# Debug_Test_Points.net
KiCad netlist of a schematic drawn in Altium Designer
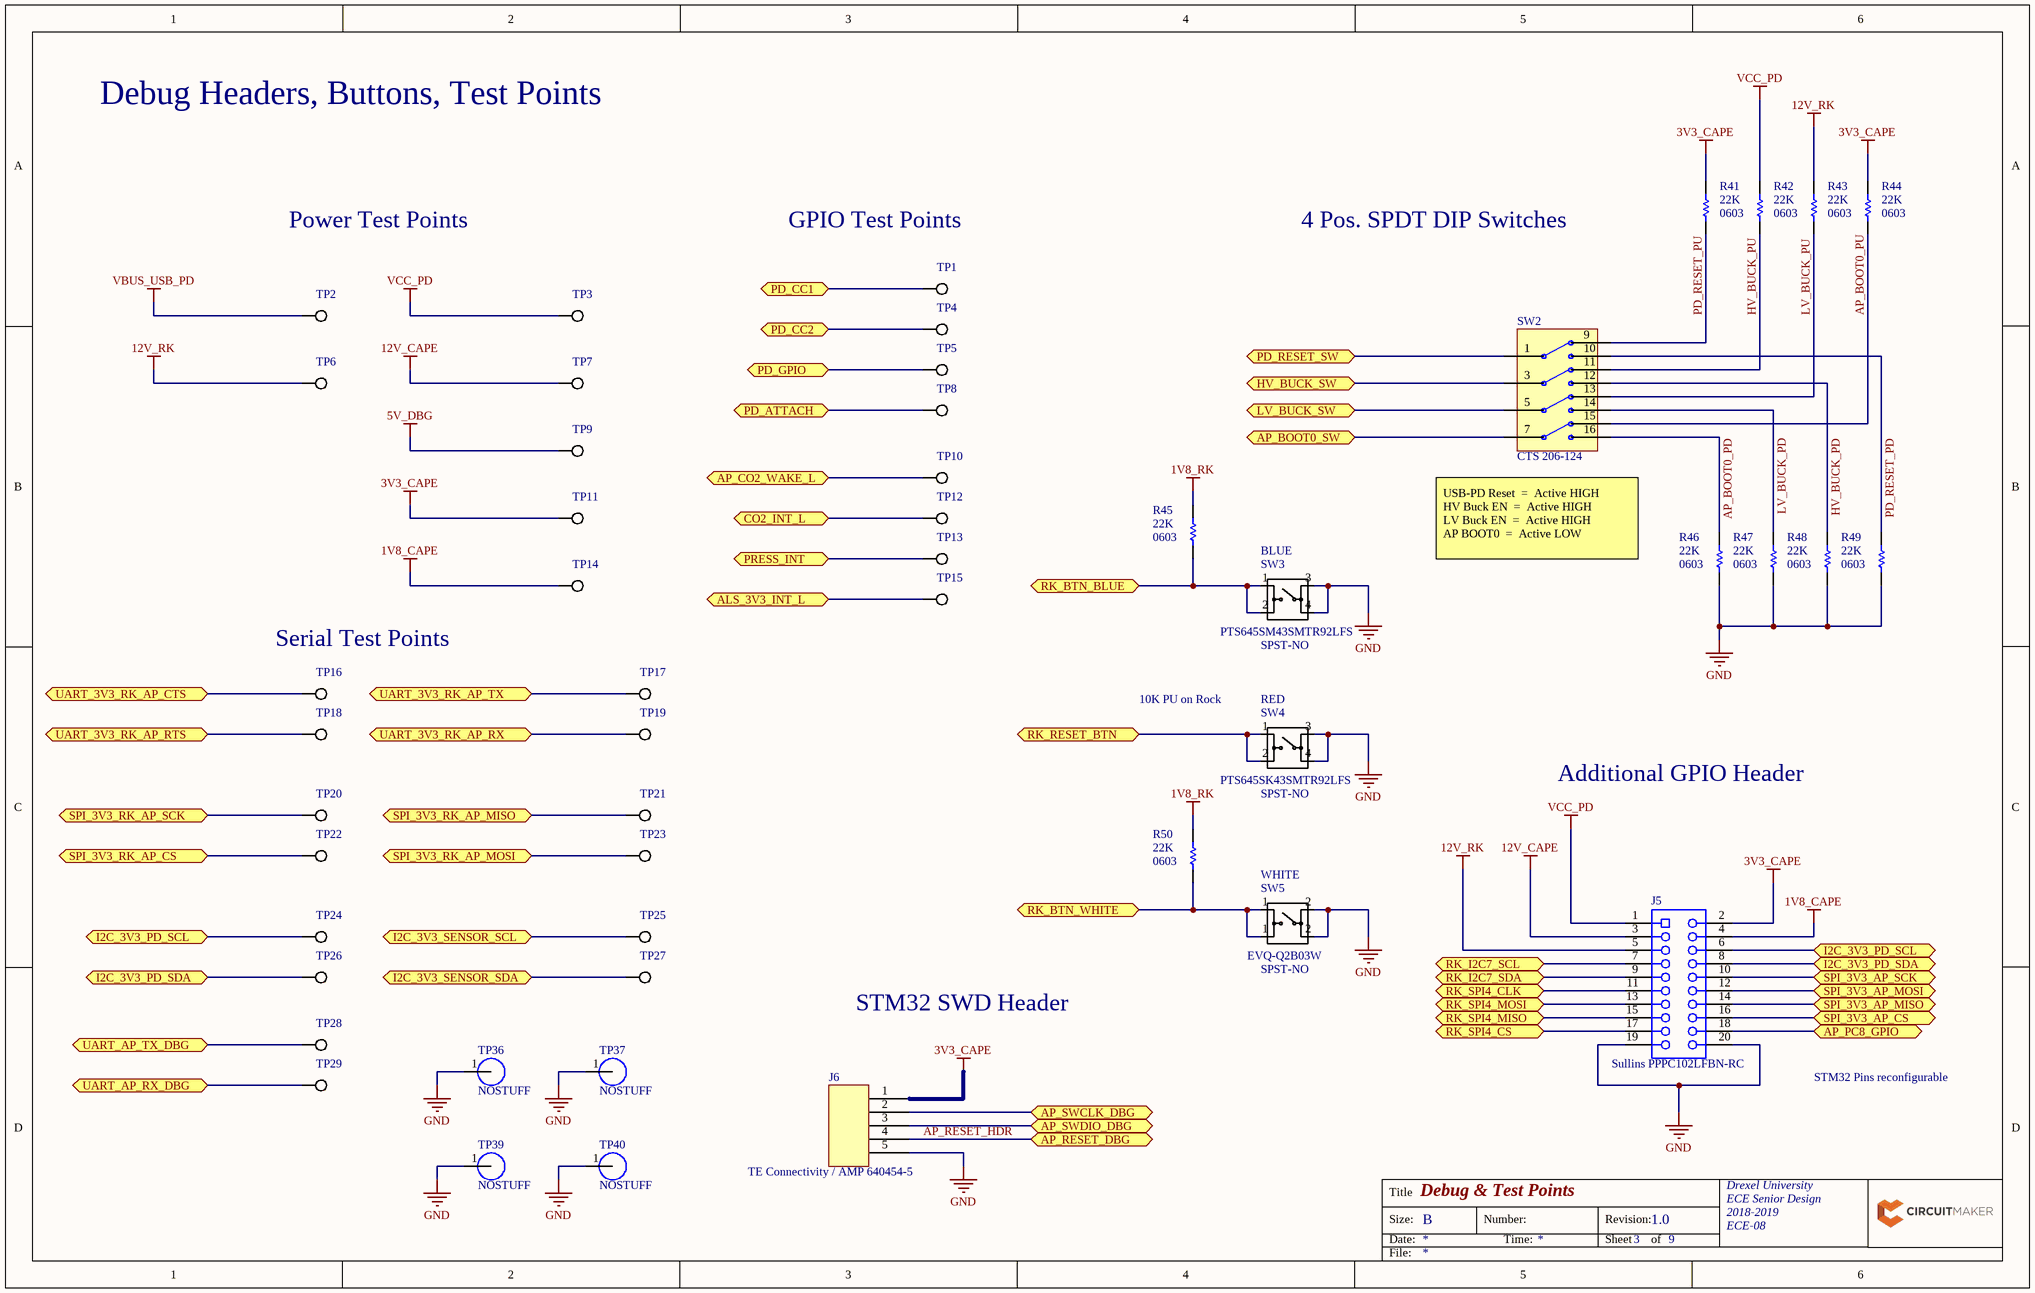
[diagram p0: Debug & Test Points.SchDoc]

(export (version "E")
  (design (tool "Eeschema 10.0.6"))
  (components
    (comp (ref "J5")
      (value "Sullins PPPC102LFBN-RC")
      (footprint "SLIN-PPPC102LFBN-RC_V")
      (fields (field (name "MANUFACTURER PART NUMBER") "PPPC102LFBN-RC"))
      (libsource (lib "CommunityVault") (part "CN-2P-F-R20"))
    )
    (comp (ref "J6")
      (value "TE Connectivity / AMP 640454-5")
      (footprint "PCB-cjz7utnpmh9dagnjcosy-1")
      (description "MTA-100 5 Position 2.54 mm Single Row Through-Hole Straight Wire to Board Header")
      (fields (field (name "MANUFACTURER PART NUMBER") "640454-5"))
      (libsource (lib "CommunityVault") (part "AMP-640454-5"))
    )
    (comp (ref "R41")
      (value "Yageo RC0603FR-0722KL")
      (footprint "RESC1608X55X25LL10T15")
      (description "Chip Resistor, 22 KOhm, +/- 1%, 0.1 W, -55 to 155 degC, 0603 (1608 Metric), RoHS, Tape and Reel")
      (fields
        (field (name "RESISTANCE") "22K")
        (field (name "CASE/PACKAGE") "0603")
        (field (name "MANUFACTURER PART NUMBER") "RC0603FR-0722KL")
      )
      (libsource (lib "CommunityVault") (part "CMP-1853446-5"))
    )
    (comp (ref "R42")
      (value "Yageo RC0603FR-0722KL")
      (footprint "RESC1608X55X25LL10T15")
      (description "Chip Resistor, 22 KOhm, +/- 1%, 0.1 W, -55 to 155 degC, 0603 (1608 Metric), RoHS, Tape and Reel")
      (fields
        (field (name "RESISTANCE") "22K")
        (field (name "CASE/PACKAGE") "0603")
        (field (name "MANUFACTURER PART NUMBER") "RC0603FR-0722KL")
      )
      (libsource (lib "CommunityVault") (part "CMP-1853446-5"))
    )
    (comp (ref "R43")
      (value "Yageo RC0603FR-0722KL")
      (footprint "RESC1608X55X25LL10T15")
      (description "Chip Resistor, 22 KOhm, +/- 1%, 0.1 W, -55 to 155 degC, 0603 (1608 Metric), RoHS, Tape and Reel")
      (fields
        (field (name "RESISTANCE") "22K")
        (field (name "CASE/PACKAGE") "0603")
        (field (name "MANUFACTURER PART NUMBER") "RC0603FR-0722KL")
      )
      (libsource (lib "CommunityVault") (part "CMP-1853446-5"))
    )
    (comp (ref "R44")
      (value "Yageo RC0603FR-0722KL")
      (footprint "RESC1608X55X25LL10T15")
      (description "Chip Resistor, 22 KOhm, +/- 1%, 0.1 W, -55 to 155 degC, 0603 (1608 Metric), RoHS, Tape and Reel")
      (fields
        (field (name "RESISTANCE") "22K")
        (field (name "CASE/PACKAGE") "0603")
        (field (name "MANUFACTURER PART NUMBER") "RC0603FR-0722KL")
      )
      (libsource (lib "CommunityVault") (part "CMP-1853446-5"))
    )
    (comp (ref "R45")
      (value "Yageo RC0603FR-0722KL")
      (footprint "RESC1608X55X25LL10T15")
      (description "Chip Resistor, 22 KOhm, +/- 1%, 0.1 W, -55 to 155 degC, 0603 (1608 Metric), RoHS, Tape and Reel")
      (fields
        (field (name "RESISTANCE") "22K")
        (field (name "CASE/PACKAGE") "0603")
        (field (name "MANUFACTURER PART NUMBER") "RC0603FR-0722KL")
      )
      (libsource (lib "CommunityVault") (part "CMP-1853446-5"))
    )
    (comp (ref "R46")
      (value "Yageo RC0603FR-0722KL")
      (footprint "RESC1608X55X25LL10T15")
      (description "Chip Resistor, 22 KOhm, +/- 1%, 0.1 W, -55 to 155 degC, 0603 (1608 Metric), RoHS, Tape and Reel")
      (fields
        (field (name "RESISTANCE") "22K")
        (field (name "CASE/PACKAGE") "0603")
        (field (name "MANUFACTURER PART NUMBER") "RC0603FR-0722KL")
      )
      (libsource (lib "CommunityVault") (part "CMP-1853446-5"))
    )
    (comp (ref "R47")
      (value "Yageo RC0603FR-0722KL")
      (footprint "RESC1608X55X25LL10T15")
      (description "Chip Resistor, 22 KOhm, +/- 1%, 0.1 W, -55 to 155 degC, 0603 (1608 Metric), RoHS, Tape and Reel")
      (fields
        (field (name "RESISTANCE") "22K")
        (field (name "CASE/PACKAGE") "0603")
        (field (name "MANUFACTURER PART NUMBER") "RC0603FR-0722KL")
      )
      (libsource (lib "CommunityVault") (part "CMP-1853446-5"))
    )
    (comp (ref "R48")
      (value "Yageo RC0603FR-0722KL")
      (footprint "RESC1608X55X25LL10T15")
      (description "Chip Resistor, 22 KOhm, +/- 1%, 0.1 W, -55 to 155 degC, 0603 (1608 Metric), RoHS, Tape and Reel")
      (fields
        (field (name "RESISTANCE") "22K")
        (field (name "CASE/PACKAGE") "0603")
        (field (name "MANUFACTURER PART NUMBER") "RC0603FR-0722KL")
      )
      (libsource (lib "CommunityVault") (part "CMP-1853446-5"))
    )
    (comp (ref "R49")
      (value "Yageo RC0603FR-0722KL")
      (footprint "RESC1608X55X25LL10T15")
      (description "Chip Resistor, 22 KOhm, +/- 1%, 0.1 W, -55 to 155 degC, 0603 (1608 Metric), RoHS, Tape and Reel")
      (fields
        (field (name "RESISTANCE") "22K")
        (field (name "CASE/PACKAGE") "0603")
        (field (name "MANUFACTURER PART NUMBER") "RC0603FR-0722KL")
      )
      (libsource (lib "CommunityVault") (part "CMP-1853446-5"))
    )
    (comp (ref "R50")
      (value "Yageo RC0603FR-0722KL")
      (footprint "RESC1608X55X25LL10T15")
      (description "Chip Resistor, 22 KOhm, +/- 1%, 0.1 W, -55 to 155 degC, 0603 (1608 Metric), RoHS, Tape and Reel")
      (fields
        (field (name "RESISTANCE") "22K")
        (field (name "CASE/PACKAGE") "0603")
        (field (name "MANUFACTURER PART NUMBER") "RC0603FR-0722KL")
      )
      (libsource (lib "CommunityVault") (part "CMP-1853446-5"))
    )
    (comp (ref "SW2")
      (value "CTS 206-124")
      (footprint "PCB-nbvsi55tyuro9im52r90-1")
      (description "Switch DIP OFF ON SPDT 4 Raised Slide 0.05A 24VDC PC Pins 10000Cycles 2.54mm Thru-Hole Tube")
      (fields (field (name "MANUFACTURER PART NUMBER") "206-124"))
      (libsource (lib "CommunityVault") (part "CMP-9d2d5432b3d942ea-1"))
    )
    (comp (ref "SW3")
      (value "C&K Components PTS645SM43SMTR92LFS")
      (footprint "PCB-s4cw3ztviwh2470uqn6q-1")
      (description "Switch Tactile N.O. SPST Round Button Gull Wing 0.05A 12VDC 100000Cycles 1.57N SMD T/R")
      (fields
        (field (name "MANUFACTURER PART NUMBER") "PTS645SM43SMTR92LFS")
        (field (name "CONTACTS TYPE") "SPST-NO")
      )
      (libsource (lib "CommunityVault") (part "CMP-3c47f600356ce380-14"))
    )
    (comp (ref "SW4")
      (value "C&K Components PTS645SK43SMTR92LFS")
      (footprint "PCB-2l25iuk5dcek232nr8ss-1")
      (description "Switch Tactile N.O SPST Round Button Gull Wing 0.05A 12VDC 100000Cycle 2.55N SMD T/R")
      (fields
        (field (name "MANUFACTURER PART NUMBER") "PTS645SK43SMTR92LFS")
        (field (name "CONTACTS TYPE") "SPST-NO")
      )
      (libsource (lib "CommunityVault") (part "CMP-8f9845df1015505f-1"))
    )
    (comp (ref "SW5")
      (value "Panasonic EVQ-Q2B03W")
      (footprint "PCB-772q97a3nev1hwheshwj-1")
      (description "Switch Tactile ON OFF SPST Round Button J-Bend 0.02A 15VDC 0.5N SMD Embossed T/R")
      (fields (field (name "MANUFACTURER PART NUMBER") "EVQ-Q2B03W") (field (name "CONTACTS TYPE") "SPST-NO"))
      (libsource (lib "CommunityVault") (part "CMP-0c8bc5972372d34c-1"))
    )
    (comp (ref "TP1")
      (value "SYM-r3tntvff39g057zxjnnx-1")
      (footprint "PCB-hew5anfrhkqvtgt23eko-1")
      (description "SMT Pad Test Point 1.27mm Diameter")
      (libsource (lib "CommunityVault") (part "SYM-r3tntvff39g057zxjnnx-1"))
    )
    (comp (ref "TP2")
      (value "SYM-r3tntvff39g057zxjnnx-1")
      (footprint "PCB-hew5anfrhkqvtgt23eko-1")
      (description "SMT Pad Test Point 1.27mm Diameter")
      (libsource (lib "CommunityVault") (part "SYM-r3tntvff39g057zxjnnx-1"))
    )
    (comp (ref "TP3")
      (value "SYM-r3tntvff39g057zxjnnx-1")
      (footprint "PCB-hew5anfrhkqvtgt23eko-1")
      (description "SMT Pad Test Point 1.27mm Diameter")
      (libsource (lib "CommunityVault") (part "SYM-r3tntvff39g057zxjnnx-1"))
    )
    (comp (ref "TP4")
      (value "SYM-r3tntvff39g057zxjnnx-1")
      (footprint "PCB-hew5anfrhkqvtgt23eko-1")
      (description "SMT Pad Test Point 1.27mm Diameter")
      (libsource (lib "CommunityVault") (part "SYM-r3tntvff39g057zxjnnx-1"))
    )
    (comp (ref "TP5")
      (value "SYM-r3tntvff39g057zxjnnx-1")
      (footprint "PCB-hew5anfrhkqvtgt23eko-1")
      (description "SMT Pad Test Point 1.27mm Diameter")
      (libsource (lib "CommunityVault") (part "SYM-r3tntvff39g057zxjnnx-1"))
    )
    (comp (ref "TP6")
      (value "SYM-r3tntvff39g057zxjnnx-1")
      (footprint "PCB-hew5anfrhkqvtgt23eko-1")
      (description "SMT Pad Test Point 1.27mm Diameter")
      (libsource (lib "CommunityVault") (part "SYM-r3tntvff39g057zxjnnx-1"))
    )
    (comp (ref "TP7")
      (value "SYM-r3tntvff39g057zxjnnx-1")
      (footprint "PCB-hew5anfrhkqvtgt23eko-1")
      (description "SMT Pad Test Point 1.27mm Diameter")
      (libsource (lib "CommunityVault") (part "SYM-r3tntvff39g057zxjnnx-1"))
    )
    (comp (ref "TP8")
      (value "SYM-r3tntvff39g057zxjnnx-1")
      (footprint "PCB-hew5anfrhkqvtgt23eko-1")
      (description "SMT Pad Test Point 1.27mm Diameter")
      (libsource (lib "CommunityVault") (part "SYM-r3tntvff39g057zxjnnx-1"))
    )
    (comp (ref "TP9")
      (value "SYM-r3tntvff39g057zxjnnx-1")
      (footprint "PCB-hew5anfrhkqvtgt23eko-1")
      (description "SMT Pad Test Point 1.27mm Diameter")
      (libsource (lib "CommunityVault") (part "SYM-r3tntvff39g057zxjnnx-1"))
    )
    (comp (ref "TP10")
      (value "SYM-r3tntvff39g057zxjnnx-1")
      (footprint "PCB-hew5anfrhkqvtgt23eko-1")
      (description "SMT Pad Test Point 1.27mm Diameter")
      (libsource (lib "CommunityVault") (part "SYM-r3tntvff39g057zxjnnx-1"))
    )
    (comp (ref "TP11")
      (value "SYM-r3tntvff39g057zxjnnx-1")
      (footprint "PCB-hew5anfrhkqvtgt23eko-1")
      (description "SMT Pad Test Point 1.27mm Diameter")
      (libsource (lib "CommunityVault") (part "SYM-r3tntvff39g057zxjnnx-1"))
    )
    (comp (ref "TP12")
      (value "SYM-r3tntvff39g057zxjnnx-1")
      (footprint "PCB-hew5anfrhkqvtgt23eko-1")
      (description "SMT Pad Test Point 1.27mm Diameter")
      (libsource (lib "CommunityVault") (part "SYM-r3tntvff39g057zxjnnx-1"))
    )
    (comp (ref "TP13")
      (value "SYM-r3tntvff39g057zxjnnx-1")
      (footprint "PCB-hew5anfrhkqvtgt23eko-1")
      (description "SMT Pad Test Point 1.27mm Diameter")
      (libsource (lib "CommunityVault") (part "SYM-r3tntvff39g057zxjnnx-1"))
    )
    (comp (ref "TP14")
      (value "SYM-r3tntvff39g057zxjnnx-1")
      (footprint "PCB-hew5anfrhkqvtgt23eko-1")
      (description "SMT Pad Test Point 1.27mm Diameter")
      (libsource (lib "CommunityVault") (part "SYM-r3tntvff39g057zxjnnx-1"))
    )
    (comp (ref "TP15")
      (value "SYM-r3tntvff39g057zxjnnx-1")
      (footprint "PCB-hew5anfrhkqvtgt23eko-1")
      (description "SMT Pad Test Point 1.27mm Diameter")
      (libsource (lib "CommunityVault") (part "SYM-r3tntvff39g057zxjnnx-1"))
    )
    (comp (ref "TP16")
      (value "SYM-r3tntvff39g057zxjnnx-1")
      (footprint "PCB-hew5anfrhkqvtgt23eko-1")
      (description "SMT Pad Test Point 1.27mm Diameter")
      (libsource (lib "CommunityVault") (part "SYM-r3tntvff39g057zxjnnx-1"))
    )
    (comp (ref "TP17")
      (value "SYM-r3tntvff39g057zxjnnx-1")
      (footprint "PCB-hew5anfrhkqvtgt23eko-1")
      (description "SMT Pad Test Point 1.27mm Diameter")
      (libsource (lib "CommunityVault") (part "SYM-r3tntvff39g057zxjnnx-1"))
    )
    (comp (ref "TP18")
      (value "SYM-r3tntvff39g057zxjnnx-1")
      (footprint "PCB-hew5anfrhkqvtgt23eko-1")
      (description "SMT Pad Test Point 1.27mm Diameter")
      (libsource (lib "CommunityVault") (part "SYM-r3tntvff39g057zxjnnx-1"))
    )
    (comp (ref "TP19")
      (value "SYM-r3tntvff39g057zxjnnx-1")
      (footprint "PCB-hew5anfrhkqvtgt23eko-1")
      (description "SMT Pad Test Point 1.27mm Diameter")
      (libsource (lib "CommunityVault") (part "SYM-r3tntvff39g057zxjnnx-1"))
    )
    (comp (ref "TP20")
      (value "SYM-r3tntvff39g057zxjnnx-1")
      (footprint "PCB-hew5anfrhkqvtgt23eko-1")
      (description "SMT Pad Test Point 1.27mm Diameter")
      (libsource (lib "CommunityVault") (part "SYM-r3tntvff39g057zxjnnx-1"))
    )
    (comp (ref "TP21")
      (value "SYM-r3tntvff39g057zxjnnx-1")
      (footprint "PCB-hew5anfrhkqvtgt23eko-1")
      (description "SMT Pad Test Point 1.27mm Diameter")
      (libsource (lib "CommunityVault") (part "SYM-r3tntvff39g057zxjnnx-1"))
    )
    (comp (ref "TP22")
      (value "SYM-r3tntvff39g057zxjnnx-1")
      (footprint "PCB-hew5anfrhkqvtgt23eko-1")
      (description "SMT Pad Test Point 1.27mm Diameter")
      (libsource (lib "CommunityVault") (part "SYM-r3tntvff39g057zxjnnx-1"))
    )
    (comp (ref "TP23")
      (value "SYM-r3tntvff39g057zxjnnx-1")
      (footprint "PCB-hew5anfrhkqvtgt23eko-1")
      (description "SMT Pad Test Point 1.27mm Diameter")
      (libsource (lib "CommunityVault") (part "SYM-r3tntvff39g057zxjnnx-1"))
    )
    (comp (ref "TP24")
      (value "SYM-r3tntvff39g057zxjnnx-1")
      (footprint "PCB-hew5anfrhkqvtgt23eko-1")
      (description "SMT Pad Test Point 1.27mm Diameter")
      (libsource (lib "CommunityVault") (part "SYM-r3tntvff39g057zxjnnx-1"))
    )
    (comp (ref "TP25")
      (value "SYM-r3tntvff39g057zxjnnx-1")
      (footprint "PCB-hew5anfrhkqvtgt23eko-1")
      (description "SMT Pad Test Point 1.27mm Diameter")
      (libsource (lib "CommunityVault") (part "SYM-r3tntvff39g057zxjnnx-1"))
    )
    (comp (ref "TP26")
      (value "SYM-r3tntvff39g057zxjnnx-1")
      (footprint "PCB-hew5anfrhkqvtgt23eko-1")
      (description "SMT Pad Test Point 1.27mm Diameter")
      (libsource (lib "CommunityVault") (part "SYM-r3tntvff39g057zxjnnx-1"))
    )
    (comp (ref "TP27")
      (value "SYM-r3tntvff39g057zxjnnx-1")
      (footprint "PCB-hew5anfrhkqvtgt23eko-1")
      (description "SMT Pad Test Point 1.27mm Diameter")
      (libsource (lib "CommunityVault") (part "SYM-r3tntvff39g057zxjnnx-1"))
    )
    (comp (ref "TP28")
      (value "SYM-r3tntvff39g057zxjnnx-1")
      (footprint "PCB-hew5anfrhkqvtgt23eko-1")
      (description "SMT Pad Test Point 1.27mm Diameter")
      (libsource (lib "CommunityVault") (part "SYM-r3tntvff39g057zxjnnx-1"))
    )
    (comp (ref "TP29")
      (value "SYM-r3tntvff39g057zxjnnx-1")
      (footprint "PCB-hew5anfrhkqvtgt23eko-1")
      (description "SMT Pad Test Point 1.27mm Diameter")
      (libsource (lib "CommunityVault") (part "SYM-r3tntvff39g057zxjnnx-1"))
    )
    (comp (ref "TP36")
      (value "Keystone 5015")
      (footprint "PCB-57fxnr3lnfj79tb7d57h-1")
      (description "Test Point; Micro Mini; SMT; Phos Bronze/Silver; 1000pc Tape & Reel")
      (fields (field (name "ALTIUM_UNNAMED_1") "NOSTUFF"))
      (libsource (lib "CommunityVault") (part "CMP-0dc8c4c22640d20f-15"))
    )
    (comp (ref "TP37")
      (value "Keystone 5015")
      (footprint "PCB-57fxnr3lnfj79tb7d57h-1")
      (description "Test Point; Micro Mini; SMT; Phos Bronze/Silver; 1000pc Tape & Reel")
      (fields (field (name "ALTIUM_UNNAMED_1") "NOSTUFF"))
      (libsource (lib "CommunityVault") (part "CMP-0dc8c4c22640d20f-15"))
    )
    (comp (ref "TP39")
      (value "Keystone 5015")
      (footprint "PCB-57fxnr3lnfj79tb7d57h-1")
      (description "Test Point; Micro Mini; SMT; Phos Bronze/Silver; 1000pc Tape & Reel")
      (fields (field (name "ALTIUM_UNNAMED_1") "NOSTUFF"))
      (libsource (lib "CommunityVault") (part "CMP-0dc8c4c22640d20f-15"))
    )
    (comp (ref "TP40")
      (value "Keystone 5015")
      (footprint "PCB-57fxnr3lnfj79tb7d57h-1")
      (description "Test Point; Micro Mini; SMT; Phos Bronze/Silver; 1000pc Tape & Reel")
      (fields (field (name "ALTIUM_UNNAMED_1") "NOSTUFF"))
      (libsource (lib "CommunityVault") (part "CMP-0dc8c4c22640d20f-15"))
    )
  )
  (nets
    (net (code "1") (name "/ALS_3V3_INT_L") (class "Default")
      (node (ref "TP15") (pin "1") (pinfunction "1_1") (pintype "passive"))
    )
    (net (code "2") (name "/AP_BOOT0_PD") (class "Default")
      (node (ref "R46") (pin "2") (pinfunction "2_2") (pintype "passive"))
      (node (ref "SW2") (pin "16") (pinfunction "16_16") (pintype "passive"))
    )
    (net (code "3") (name "/AP_BOOT0_PU") (class "Default")
      (node (ref "R44") (pin "1") (pinfunction "1_1") (pintype "passive"))
      (node (ref "SW2") (pin "15") (pinfunction "15_15") (pintype "passive"))
    )
    (net (code "4") (name "/AP_BOOT0_SW") (class "Default")
      (node (ref "SW2") (pin "7") (pinfunction "7_7") (pintype "passive"))
    )
    (net (code "5") (name "/AP_CO2_WAKE_L") (class "Default")
      (node (ref "TP10") (pin "1") (pinfunction "1_1") (pintype "passive"))
    )
    (net (code "6") (name "/AP_PC8_GPIO") (class "Default")
      (node (ref "J5") (pin "18") (pinfunction "18_18") (pintype "passive"))
    )
    (net (code "7") (name "/AP_RESET_HDR") (class "Default")
      (node (ref "J6") (pin "4") (pinfunction "4_4") (pintype "passive"))
    )
    (net (code "8") (name "/AP_SWCLK_DBG") (class "Default")
      (node (ref "J6") (pin "2") (pinfunction "2_2") (pintype "passive"))
    )
    (net (code "9") (name "/AP_SWDIO_DBG") (class "Default")
      (node (ref "J6") (pin "3") (pinfunction "3_3") (pintype "passive"))
    )
    (net (code "10") (name "/CO2_INT_L") (class "Default")
      (node (ref "TP12") (pin "1") (pinfunction "1_1") (pintype "passive"))
    )
    (net (code "11") (name "/HV_BUCK_PD") (class "Default")
      (node (ref "R48") (pin "2") (pinfunction "2_2") (pintype "passive"))
      (node (ref "SW2") (pin "12") (pinfunction "12_12") (pintype "passive"))
    )
    (net (code "12") (name "/HV_BUCK_PU") (class "Default")
      (node (ref "R42") (pin "1") (pinfunction "1_1") (pintype "passive"))
      (node (ref "SW2") (pin "11") (pinfunction "11_11") (pintype "passive"))
    )
    (net (code "13") (name "/HV_BUCK_SW") (class "Default")
      (node (ref "SW2") (pin "3") (pinfunction "3_3") (pintype "passive"))
    )
    (net (code "14") (name "/I2C_3V3_PD_SCL") (class "Default")
      (node (ref "J5") (pin "6") (pinfunction "6_6") (pintype "passive"))
      (node (ref "TP24") (pin "1") (pinfunction "1_1") (pintype "passive"))
    )
    (net (code "15") (name "/I2C_3V3_PD_SDA") (class "Default")
      (node (ref "J5") (pin "8") (pinfunction "8_8") (pintype "passive"))
      (node (ref "TP26") (pin "1") (pinfunction "1_1") (pintype "passive"))
    )
    (net (code "16") (name "/I2C_3V3_SENSOR_SCL") (class "Default")
      (node (ref "TP25") (pin "1") (pinfunction "1_1") (pintype "passive"))
    )
    (net (code "17") (name "/I2C_3V3_SENSOR_SDA") (class "Default")
      (node (ref "TP27") (pin "1") (pinfunction "1_1") (pintype "passive"))
    )
    (net (code "18") (name "/LV_BUCK_PD") (class "Default")
      (node (ref "R47") (pin "2") (pinfunction "2_2") (pintype "passive"))
      (node (ref "SW2") (pin "14") (pinfunction "14_14") (pintype "passive"))
    )
    (net (code "19") (name "/LV_BUCK_PU") (class "Default")
      (node (ref "R43") (pin "1") (pinfunction "1_1") (pintype "passive"))
      (node (ref "SW2") (pin "13") (pinfunction "13_13") (pintype "passive"))
    )
    (net (code "20") (name "/LV_BUCK_SW") (class "Default")
      (node (ref "SW2") (pin "5") (pinfunction "5_5") (pintype "passive"))
    )
    (net (code "21") (name "/PD_ATTACH") (class "Default")
      (node (ref "TP8") (pin "1") (pinfunction "1_1") (pintype "passive"))
    )
    (net (code "22") (name "/PD_CC1") (class "Default")
      (node (ref "TP1") (pin "1") (pinfunction "1_1") (pintype "passive"))
    )
    (net (code "23") (name "/PD_CC2") (class "Default")
      (node (ref "TP4") (pin "1") (pinfunction "1_1") (pintype "passive"))
    )
    (net (code "24") (name "/PD_GPIO") (class "Default")
      (node (ref "TP5") (pin "1") (pinfunction "1_1") (pintype "passive"))
    )
    (net (code "25") (name "/PD_RESET_PD") (class "Default")
      (node (ref "R49") (pin "2") (pinfunction "2_2") (pintype "passive"))
      (node (ref "SW2") (pin "10") (pinfunction "10_10") (pintype "passive"))
    )
    (net (code "26") (name "/PD_RESET_PU") (class "Default")
      (node (ref "R41") (pin "1") (pinfunction "1_1") (pintype "passive"))
      (node (ref "SW2") (pin "9") (pinfunction "9_9") (pintype "passive"))
    )
    (net (code "27") (name "/PD_RESET_SW") (class "Default")
      (node (ref "SW2") (pin "1") (pinfunction "1_1") (pintype "passive"))
    )
    (net (code "28") (name "/PRESS_INT") (class "Default")
      (node (ref "TP13") (pin "1") (pinfunction "1_1") (pintype "passive"))
    )
    (net (code "29") (name "/RK_BTN_BLUE") (class "Default")
      (node (ref "R45") (pin "1") (pinfunction "1_1") (pintype "passive"))
      (node (ref "SW3") (pin "1") (pinfunction "1_1") (pintype "passive"))
      (node (ref "SW3") (pin "2") (pinfunction "2_2") (pintype "passive"))
    )
    (net (code "30") (name "/RK_BTN_WHITE") (class "Default")
      (node (ref "R50") (pin "1") (pinfunction "1_1") (pintype "passive"))
      (node (ref "SW5") (pin "1") (pinfunction "1_1") (pintype "passive"))
    )
    (net (code "31") (name "/RK_I2C7_SCL") (class "Default")
      (node (ref "J5") (pin "7") (pinfunction "7_7") (pintype "passive"))
    )
    (net (code "32") (name "/RK_I2C7_SDA") (class "Default")
      (node (ref "J5") (pin "9") (pinfunction "9_9") (pintype "passive"))
    )
    (net (code "33") (name "/RK_RESET_BTN") (class "Default")
      (node (ref "SW4") (pin "1") (pinfunction "1_1") (pintype "passive"))
      (node (ref "SW4") (pin "2") (pinfunction "2_2") (pintype "passive"))
    )
    (net (code "34") (name "/RK_SPI4_CLK") (class "Default")
      (node (ref "J5") (pin "11") (pinfunction "11_11") (pintype "passive"))
    )
    (net (code "35") (name "/RK_SPI4_CS") (class "Default")
      (node (ref "J5") (pin "17") (pinfunction "17_17") (pintype "passive"))
    )
    (net (code "36") (name "/RK_SPI4_MISO") (class "Default")
      (node (ref "J5") (pin "15") (pinfunction "15_15") (pintype "passive"))
    )
    (net (code "37") (name "/RK_SPI4_MOSI") (class "Default")
      (node (ref "J5") (pin "13") (pinfunction "13_13") (pintype "passive"))
    )
    (net (code "38") (name "/SPI_3V3_AP_CS") (class "Default")
      (node (ref "J5") (pin "16") (pinfunction "16_16") (pintype "passive"))
    )
    (net (code "39") (name "/SPI_3V3_AP_MISO") (class "Default")
      (node (ref "J5") (pin "14") (pinfunction "14_14") (pintype "passive"))
    )
    (net (code "40") (name "/SPI_3V3_AP_MOSI") (class "Default")
      (node (ref "J5") (pin "12") (pinfunction "12_12") (pintype "passive"))
    )
    (net (code "41") (name "/SPI_3V3_AP_SCK") (class "Default")
      (node (ref "J5") (pin "10") (pinfunction "10_10") (pintype "passive"))
    )
    (net (code "42") (name "/SPI_3V3_RK_AP_CS") (class "Default")
      (node (ref "TP22") (pin "1") (pinfunction "1_1") (pintype "passive"))
    )
    (net (code "43") (name "/SPI_3V3_RK_AP_MISO") (class "Default")
      (node (ref "TP21") (pin "1") (pinfunction "1_1") (pintype "passive"))
    )
    (net (code "44") (name "/SPI_3V3_RK_AP_MOSI") (class "Default")
      (node (ref "TP23") (pin "1") (pinfunction "1_1") (pintype "passive"))
    )
    (net (code "45") (name "/SPI_3V3_RK_AP_SCK") (class "Default")
      (node (ref "TP20") (pin "1") (pinfunction "1_1") (pintype "passive"))
    )
    (net (code "46") (name "/UART_3V3_RK_AP_CTS") (class "Default")
      (node (ref "TP16") (pin "1") (pinfunction "1_1") (pintype "passive"))
    )
    (net (code "47") (name "/UART_3V3_RK_AP_RTS") (class "Default")
      (node (ref "TP18") (pin "1") (pinfunction "1_1") (pintype "passive"))
    )
    (net (code "48") (name "/UART_3V3_RK_AP_RX") (class "Default")
      (node (ref "TP19") (pin "1") (pinfunction "1_1") (pintype "passive"))
    )
    (net (code "49") (name "/UART_3V3_RK_AP_TX") (class "Default")
      (node (ref "TP17") (pin "1") (pinfunction "1_1") (pintype "passive"))
    )
    (net (code "50") (name "/UART_AP_RX_DBG") (class "Default")
      (node (ref "TP29") (pin "1") (pinfunction "1_1") (pintype "passive"))
    )
    (net (code "51") (name "/UART_AP_TX_DBG") (class "Default")
      (node (ref "TP28") (pin "1") (pinfunction "1_1") (pintype "passive"))
    )
    (net (code "52") (name "1V8_CAPE") (class "Default")
      (node (ref "J5") (pin "4") (pinfunction "4_4") (pintype "passive"))
      (node (ref "TP14") (pin "1") (pinfunction "1_1") (pintype "passive"))
    )
    (net (code "53") (name "1V8_RK") (class "Default")
      (node (ref "R45") (pin "2") (pinfunction "2_2") (pintype "passive"))
      (node (ref "R50") (pin "2") (pinfunction "2_2") (pintype "passive"))
    )
    (net (code "54") (name "3V3_CAPE") (class "Default")
      (node (ref "J5") (pin "2") (pinfunction "2_2") (pintype "passive"))
      (node (ref "J6") (pin "1") (pinfunction "1_1") (pintype "passive"))
      (node (ref "R41") (pin "2") (pinfunction "2_2") (pintype "passive"))
      (node (ref "R44") (pin "2") (pinfunction "2_2") (pintype "passive"))
      (node (ref "TP11") (pin "1") (pinfunction "1_1") (pintype "passive"))
    )
    (net (code "55") (name "5V_DBG") (class "Default")
      (node (ref "TP9") (pin "1") (pinfunction "1_1") (pintype "passive"))
    )
    (net (code "56") (name "12V_CAPE") (class "Default")
      (node (ref "J5") (pin "3") (pinfunction "3_3") (pintype "passive"))
      (node (ref "TP7") (pin "1") (pinfunction "1_1") (pintype "passive"))
    )
    (net (code "57") (name "12V_RK") (class "Default")
      (node (ref "J5") (pin "5") (pinfunction "5_5") (pintype "passive"))
      (node (ref "R43") (pin "2") (pinfunction "2_2") (pintype "passive"))
      (node (ref "TP6") (pin "1") (pinfunction "1_1") (pintype "passive"))
    )
    (net (code "58") (name "GND") (class "Default")
      (node (ref "J5") (pin "19") (pinfunction "19_19") (pintype "passive"))
      (node (ref "J5") (pin "20") (pinfunction "20_20") (pintype "passive"))
      (node (ref "J6") (pin "5") (pinfunction "5_5") (pintype "passive"))
      (node (ref "R46") (pin "1") (pinfunction "1_1") (pintype "passive"))
      (node (ref "R47") (pin "1") (pinfunction "1_1") (pintype "passive"))
      (node (ref "R48") (pin "1") (pinfunction "1_1") (pintype "passive"))
      (node (ref "R49") (pin "1") (pinfunction "1_1") (pintype "passive"))
      (node (ref "SW3") (pin "3") (pinfunction "3_3") (pintype "passive"))
      (node (ref "SW3") (pin "4") (pinfunction "4_4") (pintype "passive"))
      (node (ref "SW4") (pin "3") (pinfunction "3_3") (pintype "passive"))
      (node (ref "SW4") (pin "4") (pinfunction "4_4") (pintype "passive"))
      (node (ref "SW5") (pin "2") (pinfunction "2_2") (pintype "passive"))
      (node (ref "TP36") (pin "1") (pinfunction "1_1") (pintype "passive"))
      (node (ref "TP37") (pin "1") (pinfunction "1_1") (pintype "passive"))
      (node (ref "TP39") (pin "1") (pinfunction "1_1") (pintype "passive"))
      (node (ref "TP40") (pin "1") (pinfunction "1_1") (pintype "passive"))
    )
    (net (code "59") (name "VBUS_USB_PD") (class "Default")
      (node (ref "TP2") (pin "1") (pinfunction "1_1") (pintype "passive"))
    )
    (net (code "60") (name "VCC_PD") (class "Default")
      (node (ref "J5") (pin "1") (pinfunction "1_1") (pintype "passive"))
      (node (ref "R42") (pin "2") (pinfunction "2_2") (pintype "passive"))
      (node (ref "TP3") (pin "1") (pinfunction "1_1") (pintype "passive"))
    )
  )
)
